# ukpg.net
KiCad netlist of a schematic drawn in Altium Designer
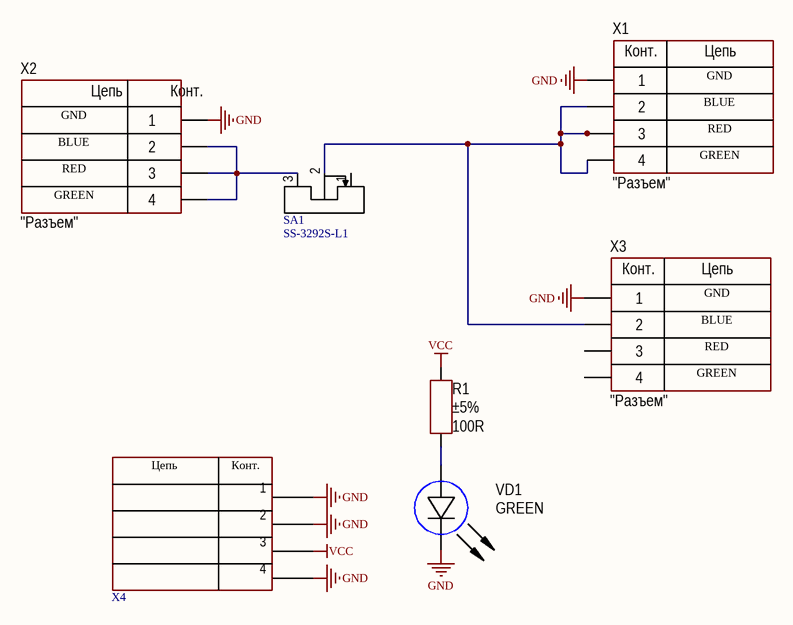
[diagram p0: ukpg.SchDoc]

(export (version "E")
  (design (tool "Eeschema 10.0.6"))
  (components
    (comp (ref "R1")
      (value "100R")
      (footprint "RES: 0603")
      (fields
        (field (name "MANUFACTURER") "Yageo")
        (field (name "PARTNUMBER") "RC0603JR-07100RL")
        (field (name "VALUEMANUFACTURERPARTNUMBER") "Resistor film, 100R, ±5%, 0603, 0.1W, -55...+125°C")
        (field (name "TOLERANCE") "±5%")
      )
      (libsource (lib "Resistor") (part "Resistor_0603"))
    )
    (comp (ref "SA1")
      (value "SS-3292S-L1")
      (footprint "SS-3292S-L1")
      (libsource (lib "switch") (part "SS-3292S-L1"))
    )
    (comp (ref "VD1")
      (value "~")
      (footprint "LED: 0805G")
      (fields
        (field (name "VALUEMANUFACTURERPARTNUMBER") "LED, *, *, *, -55...+150°C")
        (field (name "COLOR") "GREEN")
      )
      (libsource (lib "Diode") (part "LED_single"))
    )
    (comp (ref "X1")
      (value "~")
      (footprint "4PLS RIGHT ANGLE 2")
      (fields
        (field (name "MANUFACTURER") "Connfly")
        (field (name "VALUEMANUFACTURERPARTNUMBER") "Connector, 4pin, 2.54mm, 500VAC, 3A")
        (field (name "PARTNUMBER") "PLS-4")
        (field (name "COMMENTTEXT") "\"Разъем\"")
      )
      (libsource (lib "Connector") (part "PLS-4"))
    )
    (comp (ref "X2")
      (value "~")
      (footprint "CON: PBS-4 R")
      (fields
        (field (name "MANUFACTURER") "Connfly")
        (field (name "VALUEMANUFACTURERPARTNUMBER") "Connector, 4pin, 2.54mm, 500VAC, 3A")
        (field (name "PARTNUMBER") "PBS-4")
        (field (name "COMMENTTEXT") "\"Разъем\"")
      )
      (libsource (lib "Connector") (part "PBS-4"))
    )
    (comp (ref "X3")
      (value "~")
      (footprint "4PLS RIGHT ANGLE 2")
      (fields
        (field (name "MANUFACTURER") "Connfly")
        (field (name "VALUEMANUFACTURERPARTNUMBER") "Connector, 4pin, 2.54mm, 500VAC, 3A")
        (field (name "PARTNUMBER") "PLS-4")
        (field (name "COMMENTTEXT") "\"Разъем\"")
      )
      (libsource (lib "Connector") (part "PLS-4"))
    )
    (comp (ref "X4")
      (value "PBS-4 cut")
      (footprint "PBS-4 CUT")
      (libsource (lib "conect") (part "PBS-4 cut"))
    )
  )
  (nets
    (net (code "1") (name "GND") (class "Default")
      (node (ref "VD1") (pin "2") (pinfunction "C_2") (pintype "passive"))
      (node (ref "X1") (pin "1") (pinfunction "1_1") (pintype "passive"))
      (node (ref "X2") (pin "1") (pinfunction "1_1") (pintype "passive"))
      (node (ref "X3") (pin "1") (pinfunction "1_1") (pintype "passive"))
      (node (ref "X4") (pin "1") (pinfunction "1_1") (pintype "passive"))
      (node (ref "X4") (pin "2") (pinfunction "2_2") (pintype "passive"))
      (node (ref "X4") (pin "4") (pinfunction "4_4") (pintype "passive"))
    )
    (net (code "2") (name "Net-(SA1-Pad2)") (class "Default")
      (node (ref "SA1") (pin "2") (pinfunction "2_2") (pintype "passive"))
      (node (ref "X1") (pin "2") (pinfunction "2_2") (pintype "passive"))
      (node (ref "X1") (pin "3") (pinfunction "3_3") (pintype "power_in"))
      (node (ref "X1") (pin "4") (pinfunction "4_4") (pintype "power_in"))
      (node (ref "X3") (pin "2") (pinfunction "2_2") (pintype "passive"))
    )
    (net (code "3") (name "Net-(SA1-Pad3)") (class "Default")
      (node (ref "SA1") (pin "3") (pinfunction "3_3") (pintype "passive"))
      (node (ref "X2") (pin "2") (pinfunction "2_2") (pintype "passive"))
      (node (ref "X2") (pin "3") (pinfunction "3_3") (pintype "power_in"))
      (node (ref "X2") (pin "4") (pinfunction "4_4") (pintype "power_in"))
    )
    (net (code "4") (name "Net-(VD1-A)") (class "Default")
      (node (ref "R1") (pin "1") (pinfunction "1_1") (pintype "passive"))
      (node (ref "VD1") (pin "1") (pinfunction "A_1") (pintype "passive"))
    )
    (net (code "5") (name "VCC") (class "Default")
      (node (ref "R1") (pin "2") (pinfunction "2_2") (pintype "passive"))
      (node (ref "X4") (pin "3") (pinfunction "3_3") (pintype "passive"))
    )
    (net (code "6") (name "unconnected-(SA1-Pad1)") (class "Default")
      (node (ref "SA1") (pin "1") (pinfunction "1_1") (pintype "passive"))
    )
    (net (code "7") (name "unconnected-(X3-Pad3)") (class "Default")
      (node (ref "X3") (pin "3") (pinfunction "3_3") (pintype "power_in"))
    )
    (net (code "8") (name "unconnected-(X3-Pad4)") (class "Default")
      (node (ref "X3") (pin "4") (pinfunction "4_4") (pintype "power_in"))
    )
  )
)
